# io.net
KiCad netlist of a schematic drawn in Altium Designer
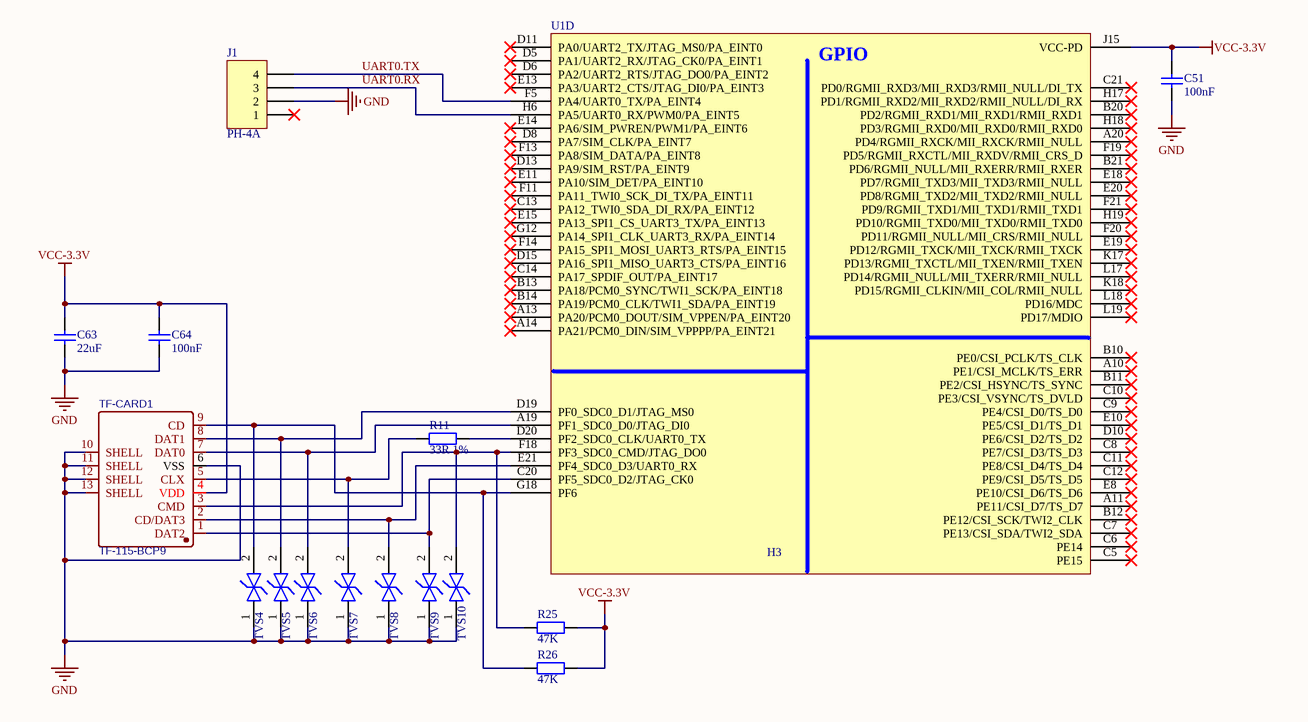
[diagram p0: io.SchDoc]

(export (version "E")
  (design (tool "Eeschema 10.0.6"))
  (components
    (comp (ref "C51")
      (value "100nF")
      (footprint "0402_C")
      (description "smd capacitor")
      (libsource (lib "Schlib") (part "CAP-SMD"))
    )
    (comp (ref "C63")
      (value "22uF")
      (footprint "0603_C")
      (description "smd capacitor")
      (libsource (lib "Schlib") (part "CAP-SMD"))
    )
    (comp (ref "C64")
      (value "100nF")
      (footprint "0402_C")
      (description "smd capacitor")
      (libsource (lib "Schlib") (part "CAP-SMD"))
    )
    (comp (ref "J1")
      (value "PH-4A")
      (footprint "CONN-TH_PH-4A")
      (description "Header, 4-Pin")
      (libsource (lib "Schlib") (part "Header-4pin"))
    )
    (comp (ref "R11")
      (value "33R 1%")
      (footprint "0402_R")
      (description "smd resistor")
      (libsource (lib "Schlib") (part "RES-SMD"))
    )
    (comp (ref "R25")
      (value "47K")
      (footprint "0402_R")
      (description "smd resistor")
      (libsource (lib "Schlib") (part "RES-SMD"))
    )
    (comp (ref "R26")
      (value "47K")
      (footprint "0402_R")
      (description "smd resistor")
      (libsource (lib "Schlib") (part "RES-SMD"))
    )
    (comp (ref "TF-CARD1")
      (value "TF-115-BCP9")
      (footprint "TF-115-BCP9")
      (description "TF card")
      (libsource (lib "Schlib") (part "TF-CARD"))
    )
    (comp (ref "TVS4")
      (value "BSD5C051L")
      (footprint "SOD-523_TVS")
      (description "Transient Voltage Suppressor")
      (libsource (lib "Schlib") (part "TVS-DIODE-SMD"))
    )
    (comp (ref "TVS5")
      (value "BSD5C051L")
      (footprint "SOD-523_TVS")
      (description "Transient Voltage Suppressor")
      (libsource (lib "Schlib") (part "TVS-DIODE-SMD"))
    )
    (comp (ref "TVS6")
      (value "BSD5C051L")
      (footprint "SOD-523_TVS")
      (description "Transient Voltage Suppressor")
      (libsource (lib "Schlib") (part "TVS-DIODE-SMD"))
    )
    (comp (ref "TVS7")
      (value "BSD5C051L")
      (footprint "SOD-523_TVS")
      (description "Transient Voltage Suppressor")
      (libsource (lib "Schlib") (part "TVS-DIODE-SMD"))
    )
    (comp (ref "TVS8")
      (value "BSD5C051L")
      (footprint "SOD-523_TVS")
      (description "Transient Voltage Suppressor")
      (libsource (lib "Schlib") (part "TVS-DIODE-SMD"))
    )
    (comp (ref "TVS9")
      (value "BSD5C051L")
      (footprint "SOD-523_TVS")
      (description "Transient Voltage Suppressor")
      (libsource (lib "Schlib") (part "TVS-DIODE-SMD"))
    )
    (comp (ref "TVS10")
      (value "BSD5C051L")
      (footprint "SOD-523_TVS")
      (description "Transient Voltage Suppressor")
      (libsource (lib "Schlib") (part "TVS-DIODE-SMD"))
    )
    (comp (ref "U1")
      (value "H3")
      (footprint "allwinner-h3")
      (description "CPU")
      (libsource (lib "Schlib") (part "H3_CPU"))
    )
  )
  (nets
    (net (code "1") (name "/UART0.RX") (class "Default")
      (node (ref "J1") (pin "3") (pinfunction "3_3") (pintype "passive"))
      (node (ref "U1") (pin "H6") (pinfunction "PA5/UART0_RX/PWM0/PA_EINT5_H6") (pintype "passive"))
    )
    (net (code "2") (name "/UART0.TX") (class "Default")
      (node (ref "J1") (pin "4") (pinfunction "4_4") (pintype "passive"))
      (node (ref "U1") (pin "F5") (pinfunction "PA4/UART0_TX/PA_EINT4_F5") (pintype "passive"))
    )
    (net (code "3") (name "GND") (class "Default")
      (node (ref "C51") (pin "2") (pintype "passive"))
      (node (ref "C63") (pin "2") (pintype "passive"))
      (node (ref "C64") (pin "2") (pintype "passive"))
      (node (ref "J1") (pin "2") (pinfunction "2_2") (pintype "passive"))
      (node (ref "TF-CARD1") (pin "10") (pinfunction "SHELL_10") (pintype "passive"))
      (node (ref "TF-CARD1") (pin "11") (pinfunction "SHELL_11") (pintype "passive"))
      (node (ref "TF-CARD1") (pin "12") (pinfunction "SHELL_12") (pintype "passive"))
      (node (ref "TF-CARD1") (pin "13") (pinfunction "SHELL_13") (pintype "passive"))
      (node (ref "TF-CARD1") (pin "6") (pinfunction "VSS_6") (pintype "passive"))
      (node (ref "TVS10") (pin "1") (pinfunction "1_1") (pintype "passive"))
      (node (ref "TVS4") (pin "1") (pinfunction "1_1") (pintype "passive"))
      (node (ref "TVS5") (pin "1") (pinfunction "1_1") (pintype "passive"))
      (node (ref "TVS6") (pin "1") (pinfunction "1_1") (pintype "passive"))
      (node (ref "TVS7") (pin "1") (pinfunction "1_1") (pintype "passive"))
      (node (ref "TVS8") (pin "1") (pinfunction "1_1") (pintype "passive"))
      (node (ref "TVS9") (pin "1") (pinfunction "1_1") (pintype "passive"))
    )
    (net (code "4") (name "Net-(TF-CARD1-CD)") (class "Default")
      (node (ref "R26") (pin "1") (pinfunction "1_1") (pintype "passive"))
      (node (ref "TF-CARD1") (pin "9") (pinfunction "CD_9") (pintype "passive"))
      (node (ref "TVS4") (pin "2") (pinfunction "2_2") (pintype "passive"))
      (node (ref "U1") (pin "G18") (pinfunction "PF6_G18") (pintype "passive"))
    )
    (net (code "5") (name "Net-(TF-CARD1-CD{slash}DAT3)") (class "Default")
      (node (ref "TF-CARD1") (pin "2") (pinfunction "CD/DAT3_2") (pintype "passive"))
      (node (ref "TVS8") (pin "2") (pinfunction "2_2") (pintype "passive"))
      (node (ref "U1") (pin "E21") (pinfunction "PF4_SDC0_D3/UART0_RX_E21") (pintype "passive"))
    )
    (net (code "6") (name "Net-(TF-CARD1-CLX)") (class "Default")
      (node (ref "R11") (pin "1") (pinfunction "1_1") (pintype "passive"))
      (node (ref "TF-CARD1") (pin "5") (pinfunction "CLX_5") (pintype "passive"))
      (node (ref "TVS7") (pin "2") (pinfunction "2_2") (pintype "passive"))
    )
    (net (code "7") (name "Net-(TF-CARD1-CMD)") (class "Default")
      (node (ref "R25") (pin "1") (pinfunction "1_1") (pintype "passive"))
      (node (ref "TF-CARD1") (pin "3") (pinfunction "CMD_3") (pintype "passive"))
      (node (ref "TVS10") (pin "2") (pinfunction "2_2") (pintype "passive"))
      (node (ref "U1") (pin "F18") (pinfunction "PF3_SDC0_CMD/JTAG_DO0_F18") (pintype "passive"))
    )
    (net (code "8") (name "Net-(TF-CARD1-DAT0)") (class "Default")
      (node (ref "TF-CARD1") (pin "7") (pinfunction "DAT0_7") (pintype "passive"))
      (node (ref "TVS6") (pin "2") (pinfunction "2_2") (pintype "passive"))
      (node (ref "U1") (pin "A19") (pinfunction "PF1_SDC0_D0/JTAG_DI0_A19") (pintype "passive"))
    )
    (net (code "9") (name "Net-(TF-CARD1-DAT1)") (class "Default")
      (node (ref "TF-CARD1") (pin "8") (pinfunction "DAT1_8") (pintype "passive"))
      (node (ref "TVS5") (pin "2") (pinfunction "2_2") (pintype "passive"))
      (node (ref "U1") (pin "D19") (pinfunction "PF0_SDC0_D1/JTAG_MS0_D19") (pintype "passive"))
    )
    (net (code "10") (name "Net-(TF-CARD1-DAT2)") (class "Default")
      (node (ref "TF-CARD1") (pin "1") (pinfunction "DAT2_1") (pintype "passive"))
      (node (ref "TVS9") (pin "2") (pinfunction "2_2") (pintype "passive"))
      (node (ref "U1") (pin "C20") (pinfunction "PF5_SDC0_D2/JTAG_CK0_C20") (pintype "passive"))
    )
    (net (code "11") (name "Net-(U1D-PF2_SDC0_CLK{slash}UART0_TX)") (class "Default")
      (node (ref "R11") (pin "2") (pinfunction "2_2") (pintype "passive"))
      (node (ref "U1") (pin "D20") (pinfunction "PF2_SDC0_CLK/UART0_TX_D20") (pintype "passive"))
    )
    (net (code "12") (name "VCC-3.3V") (class "Default")
      (node (ref "C51") (pin "1") (pintype "passive"))
      (node (ref "C63") (pin "1") (pintype "passive"))
      (node (ref "C64") (pin "1") (pintype "passive"))
      (node (ref "R25") (pin "2") (pinfunction "2_2") (pintype "passive"))
      (node (ref "R26") (pin "2") (pinfunction "2_2") (pintype "passive"))
      (node (ref "TF-CARD1") (pin "4") (pinfunction "VDD_4") (pintype "passive"))
      (node (ref "U1") (pin "J15") (pinfunction "VCC-PD_J15") (pintype "passive"))
    )
    (net (code "13") (name "unconnected-(J1-Pad1)") (class "Default")
      (node (ref "J1") (pin "1") (pinfunction "1_1") (pintype "passive+no_connect"))
    )
    (net (code "14") (name "unconnected-(U1D-PA0{slash}UART2_TX{slash}JTAG_MS0{slash}PA_EINT0-PadD11)") (class "Default")
      (node (ref "U1") (pin "D11") (pinfunction "PA0/UART2_TX/JTAG_MS0/PA_EINT0_D11") (pintype "passive+no_connect"))
    )
    (net (code "15") (name "unconnected-(U1D-PA1{slash}UART2_RX{slash}JTAG_CK0{slash}PA_EINT1-PadD5)") (class "Default")
      (node (ref "U1") (pin "D5") (pinfunction "PA1/UART2_RX/JTAG_CK0/PA_EINT1_D5") (pintype "passive+no_connect"))
    )
    (net (code "16") (name "unconnected-(U1D-PA2{slash}UART2_RTS{slash}JTAG_DO0{slash}PA_EINT2-PadD6)") (class "Default")
      (node (ref "U1") (pin "D6") (pinfunction "PA2/UART2_RTS/JTAG_DO0/PA_EINT2_D6") (pintype "passive+no_connect"))
    )
    (net (code "17") (name "unconnected-(U1D-PA3{slash}UART2_CTS{slash}JTAG_DI0{slash}PA_EINT3-PadE13)") (class "Default")
      (node (ref "U1") (pin "E13") (pinfunction "PA3/UART2_CTS/JTAG_DI0/PA_EINT3_E13") (pintype "passive+no_connect"))
    )
    (net (code "18") (name "unconnected-(U1D-PA6{slash}SIM_PWREN{slash}PWM1{slash}PA_EINT6-PadE14)") (class "Default")
      (node (ref "U1") (pin "E14") (pinfunction "PA6/SIM_PWREN/PWM1/PA_EINT6_E14") (pintype "passive+no_connect"))
    )
    (net (code "19") (name "unconnected-(U1D-PA7{slash}SIM_CLK{slash}PA_EINT7-PadD8)") (class "Default")
      (node (ref "U1") (pin "D8") (pinfunction "PA7/SIM_CLK/PA_EINT7_D8") (pintype "passive+no_connect"))
    )
    (net (code "20") (name "unconnected-(U1D-PA8{slash}SIM_DATA{slash}PA_EINT8-PadF13)") (class "Default")
      (node (ref "U1") (pin "F13") (pinfunction "PA8/SIM_DATA/PA_EINT8_F13") (pintype "passive+no_connect"))
    )
    (net (code "21") (name "unconnected-(U1D-PA9{slash}SIM_RST{slash}PA_EINT9-PadD13)") (class "Default")
      (node (ref "U1") (pin "D13") (pinfunction "PA9/SIM_RST/PA_EINT9_D13") (pintype "passive+no_connect"))
    )
    (net (code "22") (name "unconnected-(U1D-PA10{slash}SIM_DET{slash}PA_EINT10-PadE11)") (class "Default")
      (node (ref "U1") (pin "E11") (pinfunction "PA10/SIM_DET/PA_EINT10_E11") (pintype "passive+no_connect"))
    )
    (net (code "23") (name "unconnected-(U1D-PA11_TWI0_SCK_DI_TX{slash}PA_EINT11-PadF11)") (class "Default")
      (node (ref "U1") (pin "F11") (pinfunction "PA11_TWI0_SCK_DI_TX/PA_EINT11_F11") (pintype "passive+no_connect"))
    )
    (net (code "24") (name "unconnected-(U1D-PA12_TWI0_SDA_DI_RX{slash}PA_EINT12-PadC13)") (class "Default")
      (node (ref "U1") (pin "C13") (pinfunction "PA12_TWI0_SDA_DI_RX/PA_EINT12_C13") (pintype "passive+no_connect"))
    )
    (net (code "25") (name "unconnected-(U1D-PA13_SPI1_CS_UART3_TX{slash}PA_EINT13-PadE15)") (class "Default")
      (node (ref "U1") (pin "E15") (pinfunction "PA13_SPI1_CS_UART3_TX/PA_EINT13_E15") (pintype "passive+no_connect"))
    )
    (net (code "26") (name "unconnected-(U1D-PA14_SPI1_CLK_UART3_RX{slash}PA_EINT14-PadG12)") (class "Default")
      (node (ref "U1") (pin "G12") (pinfunction "PA14_SPI1_CLK_UART3_RX/PA_EINT14_G12") (pintype "passive+no_connect"))
    )
    (net (code "27") (name "unconnected-(U1D-PA15_SPI1_MOSI_UART3_RTS{slash}PA_EINT15-PadF14)") (class "Default")
      (node (ref "U1") (pin "F14") (pinfunction "PA15_SPI1_MOSI_UART3_RTS/PA_EINT15_F14") (pintype "passive+no_connect"))
    )
    (net (code "28") (name "unconnected-(U1D-PA16_SPI1_MISO_UART3_CTS{slash}PA_EINT16-PadD15)") (class "Default")
      (node (ref "U1") (pin "D15") (pinfunction "PA16_SPI1_MISO_UART3_CTS/PA_EINT16_D15") (pintype "passive+no_connect"))
    )
    (net (code "29") (name "unconnected-(U1D-PA17_SPDIF_OUT{slash}PA_EINT17-PadC14)") (class "Default")
      (node (ref "U1") (pin "C14") (pinfunction "PA17_SPDIF_OUT/PA_EINT17_C14") (pintype "passive+no_connect"))
    )
    (net (code "30") (name "unconnected-(U1D-PA18{slash}PCM0_SYNC{slash}TWI1_SCK{slash}PA_EINT18-PadB13)") (class "Default")
      (node (ref "U1") (pin "B13") (pinfunction "PA18/PCM0_SYNC/TWI1_SCK/PA_EINT18_B13") (pintype "passive+no_connect"))
    )
    (net (code "31") (name "unconnected-(U1D-PA19{slash}PCM0_CLK{slash}TWI1_SDA{slash}PA_EINT19-PadB14)") (class "Default")
      (node (ref "U1") (pin "B14") (pinfunction "PA19/PCM0_CLK/TWI1_SDA/PA_EINT19_B14") (pintype "passive+no_connect"))
    )
    (net (code "32") (name "unconnected-(U1D-PA20{slash}PCM0_DOUT{slash}SIM_VPPEN{slash}PA_EINT20-PadA13)") (class "Default")
      (node (ref "U1") (pin "A13") (pinfunction "PA20/PCM0_DOUT/SIM_VPPEN/PA_EINT20_A13") (pintype "passive+no_connect"))
    )
    (net (code "33") (name "unconnected-(U1D-PA21{slash}PCM0_DIN{slash}SIM_VPPPP{slash}PA_EINT21-PadA14)") (class "Default")
      (node (ref "U1") (pin "A14") (pinfunction "PA21/PCM0_DIN/SIM_VPPPP/PA_EINT21_A14") (pintype "passive+no_connect"))
    )
    (net (code "34") (name "unconnected-(U1D-PD0{slash}RGMII_RXD3{slash}MII_RXD3{slash}RMII_NULL{slash}DI_TX-PadC21)") (class "Default")
      (node (ref "U1") (pin "C21") (pinfunction "PD0/RGMII_RXD3/MII_RXD3/RMII_NULL/DI_TX_C21") (pintype "passive+no_connect"))
    )
    (net (code "35") (name "unconnected-(U1D-PD1{slash}RGMII_RXD2{slash}MII_RXD2{slash}RMII_NULL{slash}DI_RX-PadH17)") (class "Default")
      (node (ref "U1") (pin "H17") (pinfunction "PD1/RGMII_RXD2/MII_RXD2/RMII_NULL/DI_RX_H17") (pintype "passive+no_connect"))
    )
    (net (code "36") (name "unconnected-(U1D-PD2{slash}RGMII_RXD1{slash}MII_RXD1{slash}RMII_RXD1-PadB20)") (class "Default")
      (node (ref "U1") (pin "B20") (pinfunction "PD2/RGMII_RXD1/MII_RXD1/RMII_RXD1_B20") (pintype "passive+no_connect"))
    )
    (net (code "37") (name "unconnected-(U1D-PD3{slash}RGMII_RXD0{slash}MII_RXD0{slash}RMII_RXD0-PadH18)") (class "Default")
      (node (ref "U1") (pin "H18") (pinfunction "PD3/RGMII_RXD0/MII_RXD0/RMII_RXD0_H18") (pintype "passive+no_connect"))
    )
    (net (code "38") (name "unconnected-(U1D-PD4{slash}RGMII_RXCK{slash}MII_RXCK{slash}RMII_NULL-PadA20)") (class "Default")
      (node (ref "U1") (pin "A20") (pinfunction "PD4/RGMII_RXCK/MII_RXCK/RMII_NULL_A20") (pintype "passive+no_connect"))
    )
    (net (code "39") (name "unconnected-(U1D-PD5{slash}RGMII_RXCTL{slash}MII_RXDV{slash}RMII_CRS_D-PadF19)") (class "Default")
      (node (ref "U1") (pin "F19") (pinfunction "PD5/RGMII_RXCTL/MII_RXDV/RMII_CRS_D_F19") (pintype "passive+no_connect"))
    )
    (net (code "40") (name "unconnected-(U1D-PD6{slash}RGMII_NULL{slash}MII_RXERR{slash}RMII_RXER-PadB21)") (class "Default")
      (node (ref "U1") (pin "B21") (pinfunction "PD6/RGMII_NULL/MII_RXERR/RMII_RXER_B21") (pintype "passive+no_connect"))
    )
    (net (code "41") (name "unconnected-(U1D-PD7{slash}RGMII_TXD3{slash}MII_TXD3{slash}RMII_NULL-PadE18)") (class "Default")
      (node (ref "U1") (pin "E18") (pinfunction "PD7/RGMII_TXD3/MII_TXD3/RMII_NULL_E18") (pintype "passive+no_connect"))
    )
    (net (code "42") (name "unconnected-(U1D-PD8{slash}RGMII_TXD2{slash}MII_TXD2{slash}RMII_NULL-PadE20)") (class "Default")
      (node (ref "U1") (pin "E20") (pinfunction "PD8/RGMII_TXD2/MII_TXD2/RMII_NULL_E20") (pintype "passive+no_connect"))
    )
    (net (code "43") (name "unconnected-(U1D-PD9{slash}RGMII_TXD1{slash}MII_TXD1{slash}RMII_TXD1-PadF21)") (class "Default")
      (node (ref "U1") (pin "F21") (pinfunction "PD9/RGMII_TXD1/MII_TXD1/RMII_TXD1_F21") (pintype "passive+no_connect"))
    )
    (net (code "44") (name "unconnected-(U1D-PD10{slash}RGMII_TXD0{slash}MII_TXD0{slash}RMII_TXD0-PadH19)") (class "Default")
      (node (ref "U1") (pin "H19") (pinfunction "PD10/RGMII_TXD0/MII_TXD0/RMII_TXD0_H19") (pintype "passive+no_connect"))
    )
    (net (code "45") (name "unconnected-(U1D-PD11{slash}RGMII_NULL{slash}MII_CRS{slash}RMII_NULL-PadF20)") (class "Default")
      (node (ref "U1") (pin "F20") (pinfunction "PD11/RGMII_NULL/MII_CRS/RMII_NULL_F20") (pintype "passive+no_connect"))
    )
    (net (code "46") (name "unconnected-(U1D-PD12{slash}RGMII_TXCK{slash}MII_TXCK{slash}RMII_TXCK-PadE19)") (class "Default")
      (node (ref "U1") (pin "E19") (pinfunction "PD12/RGMII_TXCK/MII_TXCK/RMII_TXCK_E19") (pintype "passive+no_connect"))
    )
    (net (code "47") (name "unconnected-(U1D-PD13{slash}RGMII_TXCTL{slash}MII_TXEN{slash}RMII_TXEN-PadK17)") (class "Default")
      (node (ref "U1") (pin "K17") (pinfunction "PD13/RGMII_TXCTL/MII_TXEN/RMII_TXEN_K17") (pintype "passive+no_connect"))
    )
    (net (code "48") (name "unconnected-(U1D-PD14{slash}RGMII_NULL{slash}MII_TXERR{slash}RMII_NULL-PadL17)") (class "Default")
      (node (ref "U1") (pin "L17") (pinfunction "PD14/RGMII_NULL/MII_TXERR/RMII_NULL_L17") (pintype "passive+no_connect"))
    )
    (net (code "49") (name "unconnected-(U1D-PD15{slash}RGMII_CLKIN{slash}MII_COL{slash}RMII_NULL-PadK18)") (class "Default")
      (node (ref "U1") (pin "K18") (pinfunction "PD15/RGMII_CLKIN/MII_COL/RMII_NULL_K18") (pintype "passive+no_connect"))
    )
    (net (code "50") (name "unconnected-(U1D-PD16{slash}MDC-PadL18)") (class "Default")
      (node (ref "U1") (pin "L18") (pinfunction "PD16/MDC_L18") (pintype "passive+no_connect"))
    )
    (net (code "51") (name "unconnected-(U1D-PD17{slash}MDIO-PadL19)") (class "Default")
      (node (ref "U1") (pin "L19") (pinfunction "PD17/MDIO_L19") (pintype "passive+no_connect"))
    )
    (net (code "52") (name "unconnected-(U1D-PE0{slash}CSI_PCLK{slash}TS_CLK-PadB10)") (class "Default")
      (node (ref "U1") (pin "B10") (pinfunction "PE0/CSI_PCLK/TS_CLK_B10") (pintype "passive+no_connect"))
    )
    (net (code "53") (name "unconnected-(U1D-PE1{slash}CSI_MCLK{slash}TS_ERR-PadA10)") (class "Default")
      (node (ref "U1") (pin "A10") (pinfunction "PE1/CSI_MCLK/TS_ERR_A10") (pintype "passive+no_connect"))
    )
    (net (code "54") (name "unconnected-(U1D-PE2{slash}CSI_HSYNC{slash}TS_SYNC-PadB11)") (class "Default")
      (node (ref "U1") (pin "B11") (pinfunction "PE2/CSI_HSYNC/TS_SYNC_B11") (pintype "passive+no_connect"))
    )
    (net (code "55") (name "unconnected-(U1D-PE3{slash}CSI_VSYNC{slash}TS_DVLD-PadC10)") (class "Default")
      (node (ref "U1") (pin "C10") (pinfunction "PE3/CSI_VSYNC/TS_DVLD_C10") (pintype "passive+no_connect"))
    )
    (net (code "56") (name "unconnected-(U1D-PE4{slash}CSI_D0{slash}TS_D0-PadC9)") (class "Default")
      (node (ref "U1") (pin "C9") (pinfunction "PE4/CSI_D0/TS_D0_C9") (pintype "passive+no_connect"))
    )
    (net (code "57") (name "unconnected-(U1D-PE5{slash}CSI_D1{slash}TS_D1-PadE10)") (class "Default")
      (node (ref "U1") (pin "E10") (pinfunction "PE5/CSI_D1/TS_D1_E10") (pintype "passive+no_connect"))
    )
    (net (code "58") (name "unconnected-(U1D-PE6{slash}CSI_D2{slash}TS_D2-PadD10)") (class "Default")
      (node (ref "U1") (pin "D10") (pinfunction "PE6/CSI_D2/TS_D2_D10") (pintype "passive+no_connect"))
    )
    (net (code "59") (name "unconnected-(U1D-PE7{slash}CSI_D3{slash}TS_D3-PadC8)") (class "Default")
      (node (ref "U1") (pin "C8") (pinfunction "PE7/CSI_D3/TS_D3_C8") (pintype "passive+no_connect"))
    )
    (net (code "60") (name "unconnected-(U1D-PE8{slash}CSI_D4{slash}TS_D4-PadC11)") (class "Default")
      (node (ref "U1") (pin "C11") (pinfunction "PE8/CSI_D4/TS_D4_C11") (pintype "passive+no_connect"))
    )
    (net (code "61") (name "unconnected-(U1D-PE9{slash}CSI_D5{slash}TS_D5-PadC12)") (class "Default")
      (node (ref "U1") (pin "C12") (pinfunction "PE9/CSI_D5/TS_D5_C12") (pintype "passive+no_connect"))
    )
    (net (code "62") (name "unconnected-(U1D-PE10{slash}CSI_D6{slash}TS_D6-PadE8)") (class "Default")
      (node (ref "U1") (pin "E8") (pinfunction "PE10/CSI_D6/TS_D6_E8") (pintype "passive+no_connect"))
    )
    (net (code "63") (name "unconnected-(U1D-PE11{slash}CSI_D7{slash}TS_D7-PadA11)") (class "Default")
      (node (ref "U1") (pin "A11") (pinfunction "PE11/CSI_D7/TS_D7_A11") (pintype "passive+no_connect"))
    )
    (net (code "64") (name "unconnected-(U1D-PE12{slash}CSI_SCK{slash}TWI2_CLK-PadB12)") (class "Default")
      (node (ref "U1") (pin "B12") (pinfunction "PE12/CSI_SCK/TWI2_CLK_B12") (pintype "passive+no_connect"))
    )
    (net (code "65") (name "unconnected-(U1D-PE13{slash}CSI_SDA{slash}TWI2_SDA-PadC7)") (class "Default")
      (node (ref "U1") (pin "C7") (pinfunction "PE13/CSI_SDA/TWI2_SDA_C7") (pintype "passive+no_connect"))
    )
    (net (code "66") (name "unconnected-(U1D-PE14-PadC6)") (class "Default")
      (node (ref "U1") (pin "C6") (pinfunction "PE14_C6") (pintype "passive+no_connect"))
    )
    (net (code "67") (name "unconnected-(U1D-PE15-PadC5)") (class "Default")
      (node (ref "U1") (pin "C5") (pinfunction "PE15_C5") (pintype "passive+no_connect"))
    )
  )
)
